# crown-C.net
KiCad netlist of a schematic drawn in EAGLE
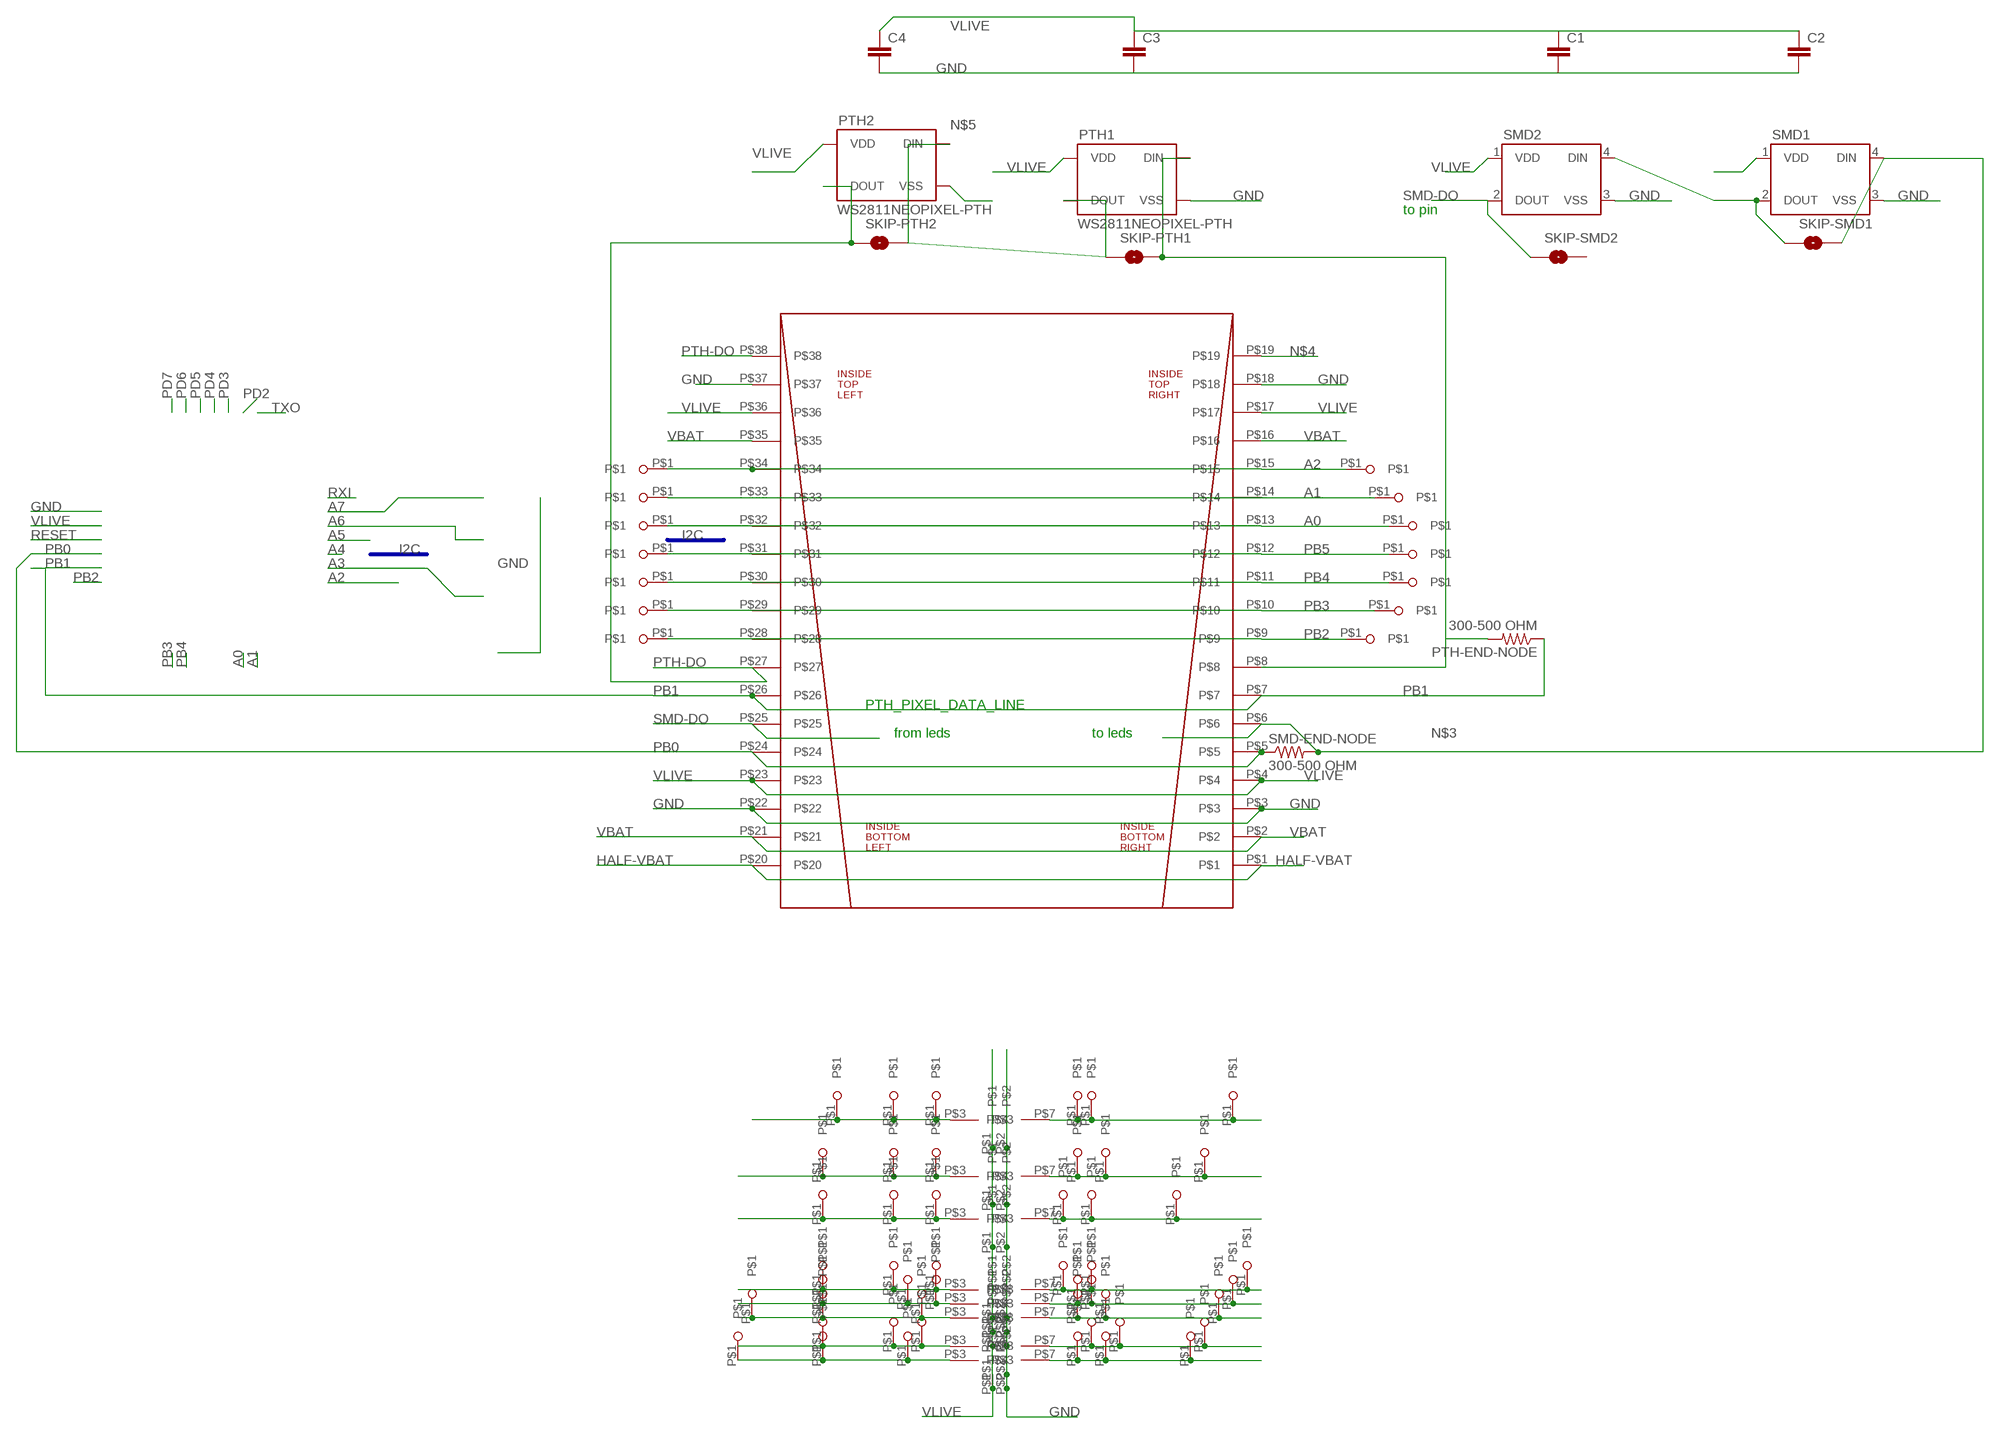
[diagram p0: schematic, sheet 1]

(export (version "E")
  (design (tool "Eeschema 10.0.6"))
  (components
    (comp (ref "C1")
      (value "CAP0805")
      (footprint "eagle-import:0805")
      (libsource (lib "eagle-import") (part "CAP0805"))
    )
    (comp (ref "C2")
      (value "CAP0805")
      (footprint "eagle-import:0805")
      (libsource (lib "eagle-import") (part "CAP0805"))
    )
    (comp (ref "C3")
      (value "CAP0805")
      (footprint "eagle-import:0805")
      (libsource (lib "eagle-import") (part "CAP0805"))
    )
    (comp (ref "C4")
      (value "CAP0805")
      (footprint "eagle-import:0805")
      (libsource (lib "eagle-import") (part "CAP0805"))
    )
    (comp (ref "PTH-END-NODE")
      (value "300-500 OHM")
      (footprint "eagle-import:0805")
      (libsource (lib "eagle-import") (part "RESISTOR0805-RES"))
    )
    (comp (ref "PTH1")
      (value "WS2811NEOPIXEL-PTH")
      (footprint "eagle-import:WS2811-PTH-FLAT")
      (libsource (lib "eagle-import") (part "WS2811NEOPIXEL-PTH"))
    )
    (comp (ref "PTH2")
      (value "WS2811NEOPIXEL-PTH")
      (footprint "eagle-import:WS2811-PTH-FLAT")
      (libsource (lib "eagle-import") (part "WS2811NEOPIXEL-PTH"))
    )
    (comp (ref "SKIP-PTH1")
      (value "SOLDERJUMPERNC2")
      (footprint "eagle-import:SJ_2S-NOTRACE")
      (libsource (lib "eagle-import") (part "SOLDERJUMPERNC2"))
    )
    (comp (ref "SKIP-PTH2")
      (value "SOLDERJUMPERNC2")
      (footprint "eagle-import:SJ_2S-NOTRACE")
      (libsource (lib "eagle-import") (part "SOLDERJUMPERNC2"))
    )
    (comp (ref "SKIP-SMD1")
      (value "SOLDERJUMPERNC2")
      (footprint "eagle-import:SJ_2S-NOTRACE")
      (libsource (lib "eagle-import") (part "SOLDERJUMPERNC2"))
    )
    (comp (ref "SKIP-SMD2")
      (value "SOLDERJUMPERNC2")
      (footprint "eagle-import:SJ_2S-NOTRACE")
      (libsource (lib "eagle-import") (part "SOLDERJUMPERNC2"))
    )
    (comp (ref "SMD-END-NODE")
      (value "300-500 OHM")
      (footprint "eagle-import:0805")
      (libsource (lib "eagle-import") (part "RESISTOR0805-RES"))
    )
    (comp (ref "SMD1")
      (value "WS2812B")
      (footprint "eagle-import:WS2812B")
      (libsource (lib "eagle-import") (part "WS2812B"))
    )
    (comp (ref "SMD2")
      (value "WS2812B")
      (footprint "eagle-import:WS2812B")
      (libsource (lib "eagle-import") (part "WS2812B"))
    )
    (comp (ref "U$1")
      (value "SMD_BREADBOARD")
      (footprint "eagle-import:SMD_BREADBOARD_4X")
      (libsource (lib "eagle-import") (part "SMD_BREADBOARD"))
    )
    (comp (ref "U$2")
      (value "CROWNSTANDARD")
      (footprint "eagle-import:CROWN")
      (libsource (lib "eagle-import") (part "CROWNSTANDARD"))
    )
    (comp (ref "U$3")
      (value "SMD_BREADBOARD")
      (footprint "eagle-import:SMD_BREADBOARD_4X")
      (libsource (lib "eagle-import") (part "SMD_BREADBOARD"))
    )
    (comp (ref "U$4")
      (value "SMD_BREADBOARD")
      (footprint "eagle-import:SMD_BREADBOARD_4X")
      (libsource (lib "eagle-import") (part "SMD_BREADBOARD"))
    )
    (comp (ref "U$5")
      (value "SMD_BREADBOARD")
      (footprint "eagle-import:SMD_BREADBOARD_4X")
      (libsource (lib "eagle-import") (part "SMD_BREADBOARD"))
    )
    (comp (ref "U$6")
      (value "SMD_BREADBOARD")
      (footprint "eagle-import:SMD_BREADBOARD_4X")
      (libsource (lib "eagle-import") (part "SMD_BREADBOARD"))
    )
    (comp (ref "U$7")
      (value "SMD_BREADBOARD")
      (footprint "eagle-import:SMD_BREADBOARD_4X")
      (libsource (lib "eagle-import") (part "SMD_BREADBOARD"))
    )
    (comp (ref "U$8")
      (value "SMD_BREADBOARD")
      (footprint "eagle-import:SMD_BREADBOARD_4X")
      (libsource (lib "eagle-import") (part "SMD_BREADBOARD"))
    )
    (comp (ref "U$9")
      (value "SMD_BREADBOARD")
      (footprint "eagle-import:SMD_BREADBOARD_4X")
      (libsource (lib "eagle-import") (part "SMD_BREADBOARD"))
    )
    (comp (ref "U$10")
      (value "SMD_PAD")
      (footprint "eagle-import:SMD_BREADBOARD_PAD")
      (libsource (lib "eagle-import") (part "SMD_PAD"))
    )
    (comp (ref "U$11")
      (value "SMD_PAD")
      (footprint "eagle-import:SMD_BREADBOARD_PAD")
      (libsource (lib "eagle-import") (part "SMD_PAD"))
    )
    (comp (ref "U$12")
      (value "SMD_PAD")
      (footprint "eagle-import:SMD_BREADBOARD_PAD")
      (libsource (lib "eagle-import") (part "SMD_PAD"))
    )
    (comp (ref "U$13")
      (value "SMD_PAD")
      (footprint "eagle-import:SMD_BREADBOARD_PAD")
      (libsource (lib "eagle-import") (part "SMD_PAD"))
    )
    (comp (ref "U$14")
      (value "SMD_PAD")
      (footprint "eagle-import:SMD_BREADBOARD_PAD")
      (libsource (lib "eagle-import") (part "SMD_PAD"))
    )
    (comp (ref "U$15")
      (value "SMD_PAD")
      (footprint "eagle-import:SMD_BREADBOARD_PAD")
      (libsource (lib "eagle-import") (part "SMD_PAD"))
    )
    (comp (ref "U$16")
      (value "SMD_PAD")
      (footprint "eagle-import:SMD_BREADBOARD_PAD")
      (libsource (lib "eagle-import") (part "SMD_PAD"))
    )
    (comp (ref "U$17")
      (value "SMD_PAD")
      (footprint "eagle-import:SMD_BREADBOARD_PAD")
      (libsource (lib "eagle-import") (part "SMD_PAD"))
    )
    (comp (ref "U$18")
      (value "SMD_PAD")
      (footprint "eagle-import:SMD_BREADBOARD_PAD")
      (libsource (lib "eagle-import") (part "SMD_PAD"))
    )
    (comp (ref "U$19")
      (value "SMD_PAD")
      (footprint "eagle-import:SMD_BREADBOARD_PAD")
      (libsource (lib "eagle-import") (part "SMD_PAD"))
    )
    (comp (ref "U$20")
      (value "SMD_PAD")
      (footprint "eagle-import:SMD_BREADBOARD_PAD")
      (libsource (lib "eagle-import") (part "SMD_PAD"))
    )
    (comp (ref "U$21")
      (value "SMD_PAD")
      (footprint "eagle-import:SMD_BREADBOARD_PAD")
      (libsource (lib "eagle-import") (part "SMD_PAD"))
    )
    (comp (ref "U$22")
      (value "SMD_PAD")
      (footprint "eagle-import:SMD_BREADBOARD_PAD")
      (libsource (lib "eagle-import") (part "SMD_PAD"))
    )
    (comp (ref "U$23")
      (value "SMD_PAD")
      (footprint "eagle-import:SMD_BREADBOARD_PAD")
      (libsource (lib "eagle-import") (part "SMD_PAD"))
    )
    (comp (ref "U$24")
      (value "SMD_PAD")
      (footprint "eagle-import:SMD_BREADBOARD_PAD")
      (libsource (lib "eagle-import") (part "SMD_PAD"))
    )
    (comp (ref "U$25")
      (value "SMD_PAD")
      (footprint "eagle-import:SMD_BREADBOARD_PAD")
      (libsource (lib "eagle-import") (part "SMD_PAD"))
    )
    (comp (ref "U$26")
      (value "SMD_PAD")
      (footprint "eagle-import:SMD_BREADBOARD_PAD")
      (libsource (lib "eagle-import") (part "SMD_PAD"))
    )
    (comp (ref "U$27")
      (value "SMD_PAD")
      (footprint "eagle-import:SMD_BREADBOARD_PAD")
      (libsource (lib "eagle-import") (part "SMD_PAD"))
    )
    (comp (ref "U$28")
      (value "SMD_PAD")
      (footprint "eagle-import:SMD_BREADBOARD_PAD")
      (libsource (lib "eagle-import") (part "SMD_PAD"))
    )
    (comp (ref "U$29")
      (value "SMD_PAD")
      (footprint "eagle-import:SMD_BREADBOARD_PAD")
      (libsource (lib "eagle-import") (part "SMD_PAD"))
    )
    (comp (ref "U$30")
      (value "SMD_PAD")
      (footprint "eagle-import:SMD_BREADBOARD_PAD")
      (libsource (lib "eagle-import") (part "SMD_PAD"))
    )
    (comp (ref "U$31")
      (value "SMD_PAD")
      (footprint "eagle-import:SMD_BREADBOARD_PAD")
      (libsource (lib "eagle-import") (part "SMD_PAD"))
    )
    (comp (ref "U$32")
      (value "SMD_PAD")
      (footprint "eagle-import:SMD_BREADBOARD_PAD")
      (libsource (lib "eagle-import") (part "SMD_PAD"))
    )
    (comp (ref "U$33")
      (value "SMD_PAD")
      (footprint "eagle-import:SMD_BREADBOARD_PAD")
      (libsource (lib "eagle-import") (part "SMD_PAD"))
    )
    (comp (ref "U$34")
      (value "SMD_PAD")
      (footprint "eagle-import:SMD_BREADBOARD_PAD")
      (libsource (lib "eagle-import") (part "SMD_PAD"))
    )
    (comp (ref "U$35")
      (value "SMD_PAD")
      (footprint "eagle-import:SMD_BREADBOARD_PAD")
      (libsource (lib "eagle-import") (part "SMD_PAD"))
    )
    (comp (ref "U$36")
      (value "SMD_PAD")
      (footprint "eagle-import:SMD_BREADBOARD_PAD")
      (libsource (lib "eagle-import") (part "SMD_PAD"))
    )
    (comp (ref "U$37")
      (value "SMD_PAD")
      (footprint "eagle-import:SMD_BREADBOARD_PAD")
      (libsource (lib "eagle-import") (part "SMD_PAD"))
    )
    (comp (ref "U$38")
      (value "SMD_PAD")
      (footprint "eagle-import:SMD_BREADBOARD_PAD")
      (libsource (lib "eagle-import") (part "SMD_PAD"))
    )
    (comp (ref "U$39")
      (value "SMD_PAD")
      (footprint "eagle-import:SMD_BREADBOARD_PAD")
      (libsource (lib "eagle-import") (part "SMD_PAD"))
    )
    (comp (ref "U$40")
      (value "SMD_PAD")
      (footprint "eagle-import:SMD_BREADBOARD_PAD")
      (libsource (lib "eagle-import") (part "SMD_PAD"))
    )
    (comp (ref "U$41")
      (value "SMD_PAD")
      (footprint "eagle-import:SMD_BREADBOARD_PAD")
      (libsource (lib "eagle-import") (part "SMD_PAD"))
    )
    (comp (ref "U$42")
      (value "SMD_PAD")
      (footprint "eagle-import:SMD_BREADBOARD_PAD")
      (libsource (lib "eagle-import") (part "SMD_PAD"))
    )
    (comp (ref "U$43")
      (value "SMD_PAD")
      (footprint "eagle-import:SMD_BREADBOARD_PAD")
      (libsource (lib "eagle-import") (part "SMD_PAD"))
    )
    (comp (ref "U$44")
      (value "SMD_PAD")
      (footprint "eagle-import:SMD_BREADBOARD_PAD")
      (libsource (lib "eagle-import") (part "SMD_PAD"))
    )
    (comp (ref "U$45")
      (value "SMD_PAD")
      (footprint "eagle-import:SMD_BREADBOARD_PAD")
      (libsource (lib "eagle-import") (part "SMD_PAD"))
    )
    (comp (ref "U$46")
      (value "SMD_PAD")
      (footprint "eagle-import:SMD_BREADBOARD_PAD")
      (libsource (lib "eagle-import") (part "SMD_PAD"))
    )
    (comp (ref "U$47")
      (value "SMD_PAD")
      (footprint "eagle-import:SMD_BREADBOARD_PAD")
      (libsource (lib "eagle-import") (part "SMD_PAD"))
    )
    (comp (ref "U$48")
      (value "SMD_PAD")
      (footprint "eagle-import:SMD_BREADBOARD_PAD")
      (libsource (lib "eagle-import") (part "SMD_PAD"))
    )
    (comp (ref "U$49")
      (value "SMD_PAD")
      (footprint "eagle-import:SMD_BREADBOARD_PAD")
      (libsource (lib "eagle-import") (part "SMD_PAD"))
    )
    (comp (ref "U$50")
      (value "SMD_PAD")
      (footprint "eagle-import:SMD_BREADBOARD_PAD")
      (libsource (lib "eagle-import") (part "SMD_PAD"))
    )
    (comp (ref "U$51")
      (value "SMD_PAD")
      (footprint "eagle-import:SMD_BREADBOARD_PAD")
      (libsource (lib "eagle-import") (part "SMD_PAD"))
    )
    (comp (ref "U$52")
      (value "SMD_PAD")
      (footprint "eagle-import:SMD_BREADBOARD_PAD")
      (libsource (lib "eagle-import") (part "SMD_PAD"))
    )
    (comp (ref "U$53")
      (value "SMD_PAD")
      (footprint "eagle-import:SMD_BREADBOARD_PAD")
      (libsource (lib "eagle-import") (part "SMD_PAD"))
    )
    (comp (ref "U$54")
      (value "SMD_PAD")
      (footprint "eagle-import:SMD_BREADBOARD_PAD")
      (libsource (lib "eagle-import") (part "SMD_PAD"))
    )
    (comp (ref "U$55")
      (value "SMD_PAD")
      (footprint "eagle-import:SMD_BREADBOARD_PAD")
      (libsource (lib "eagle-import") (part "SMD_PAD"))
    )
    (comp (ref "U$56")
      (value "SMD_PAD")
      (footprint "eagle-import:SMD_BREADBOARD_PAD")
      (libsource (lib "eagle-import") (part "SMD_PAD"))
    )
    (comp (ref "U$57")
      (value "SMD_PAD")
      (footprint "eagle-import:SMD_BREADBOARD_PAD")
      (libsource (lib "eagle-import") (part "SMD_PAD"))
    )
    (comp (ref "U$58")
      (value "SMD_PAD")
      (footprint "eagle-import:SMD_BREADBOARD_PAD")
      (libsource (lib "eagle-import") (part "SMD_PAD"))
    )
    (comp (ref "U$59")
      (value "SMD_PAD")
      (footprint "eagle-import:SMD_BREADBOARD_PAD")
      (libsource (lib "eagle-import") (part "SMD_PAD"))
    )
    (comp (ref "U$60")
      (value "SMD_PAD")
      (footprint "eagle-import:SMD_BREADBOARD_PAD")
      (libsource (lib "eagle-import") (part "SMD_PAD"))
    )
    (comp (ref "U$61")
      (value "SMD_PAD")
      (footprint "eagle-import:SMD_BREADBOARD_PAD")
      (libsource (lib "eagle-import") (part "SMD_PAD"))
    )
    (comp (ref "U$62")
      (value "SMD_PAD")
      (footprint "eagle-import:SMD_BREADBOARD_PAD")
      (libsource (lib "eagle-import") (part "SMD_PAD"))
    )
    (comp (ref "U$63")
      (value "SMD_PAD")
      (footprint "eagle-import:SMD_BREADBOARD_PAD")
      (libsource (lib "eagle-import") (part "SMD_PAD"))
    )
    (comp (ref "U$64")
      (value "SMD_PAD")
      (footprint "eagle-import:SMD_BREADBOARD_PAD")
      (libsource (lib "eagle-import") (part "SMD_PAD"))
    )
    (comp (ref "U$65")
      (value "SMD_PAD")
      (footprint "eagle-import:SMD_BREADBOARD_PAD")
      (libsource (lib "eagle-import") (part "SMD_PAD"))
    )
    (comp (ref "U$66")
      (value "SMD_PAD")
      (footprint "eagle-import:SMD_BREADBOARD_PAD")
      (libsource (lib "eagle-import") (part "SMD_PAD"))
    )
    (comp (ref "U$67")
      (value "SMD_PAD")
      (footprint "eagle-import:SMD_BREADBOARD_PAD")
      (libsource (lib "eagle-import") (part "SMD_PAD"))
    )
    (comp (ref "U$68")
      (value "SMD_PAD")
      (footprint "eagle-import:SMD_BREADBOARD_PAD")
      (libsource (lib "eagle-import") (part "SMD_PAD"))
    )
    (comp (ref "U$69")
      (value "SMD_PAD")
      (footprint "eagle-import:SMD_BREADBOARD_PAD")
      (libsource (lib "eagle-import") (part "SMD_PAD"))
    )
    (comp (ref "U$70")
      (value "SMD_PAD")
      (footprint "eagle-import:SMD_BREADBOARD_PAD")
      (libsource (lib "eagle-import") (part "SMD_PAD"))
    )
    (comp (ref "U$71")
      (value "SMD_PAD")
      (footprint "eagle-import:SMD_BREADBOARD_PAD")
      (libsource (lib "eagle-import") (part "SMD_PAD"))
    )
  )
  (nets
    (net (code "2") (name "/A0") (class "Default")
      (node (ref "U$2") (pin "P$13") (pinfunction "P$13_P$13") (pintype "bidirectional"))
      (node (ref "U$2") (pin "P$32") (pinfunction "P$32_P$32") (pintype "bidirectional"))
      (node (ref "U$44") (pin "P$1") (pinfunction "P$1_P$1") (pintype "bidirectional"))
      (node (ref "U$55") (pin "P$1") (pinfunction "P$1_P$1") (pintype "bidirectional"))
    )
    (net (code "3") (name "/A1") (class "Default")
      (node (ref "U$2") (pin "P$14") (pinfunction "P$14_P$14") (pintype "bidirectional"))
      (node (ref "U$2") (pin "P$33") (pinfunction "P$33_P$33") (pintype "bidirectional"))
      (node (ref "U$43") (pin "P$1") (pinfunction "P$1_P$1") (pintype "bidirectional"))
      (node (ref "U$56") (pin "P$1") (pinfunction "P$1_P$1") (pintype "bidirectional"))
    )
    (net (code "4") (name "/A2") (class "Default")
      (node (ref "U$2") (pin "P$15") (pinfunction "P$15_P$15") (pintype "bidirectional"))
      (node (ref "U$2") (pin "P$34") (pinfunction "P$34_P$34") (pintype "bidirectional"))
      (node (ref "U$42") (pin "P$1") (pinfunction "P$1_P$1") (pintype "bidirectional"))
      (node (ref "U$58") (pin "P$1") (pinfunction "P$1_P$1") (pintype "bidirectional"))
    )
    (net (code "10") (name "/GND") (class "Default")
      (node (ref "C1") (pin "2") (pinfunction "2_2") (pintype "passive"))
      (node (ref "C2") (pin "2") (pinfunction "2_2") (pintype "passive"))
      (node (ref "C3") (pin "2") (pinfunction "2_2") (pintype "passive"))
      (node (ref "C4") (pin "2") (pinfunction "2_2") (pintype "passive"))
      (node (ref "PTH1") (pin "P$2") (pinfunction "VSS_P$2") (pintype "power_in"))
      (node (ref "PTH1") (pin "P$6") (pinfunction "VSS_P$6") (pintype "power_in"))
      (node (ref "PTH2") (pin "P$2") (pinfunction "VSS_P$2") (pintype "power_in"))
      (node (ref "PTH2") (pin "P$6") (pinfunction "VSS_P$6") (pintype "power_in"))
      (node (ref "SMD1") (pin "3") (pinfunction "VSS_3") (pintype "power_in"))
      (node (ref "SMD2") (pin "3") (pinfunction "VSS_3") (pintype "power_in"))
      (node (ref "U$1") (pin "P$2") (pinfunction "P$2_P$2") (pintype "bidirectional"))
      (node (ref "U$2") (pin "P$18") (pinfunction "P$18_P$18") (pintype "bidirectional"))
      (node (ref "U$2") (pin "P$22") (pinfunction "P$22_P$22") (pintype "bidirectional"))
      (node (ref "U$2") (pin "P$3") (pinfunction "P$3_P$3") (pintype "bidirectional"))
      (node (ref "U$2") (pin "P$37") (pinfunction "P$37_P$37") (pintype "bidirectional"))
      (node (ref "U$3") (pin "P$2") (pinfunction "P$2_P$2") (pintype "bidirectional"))
      (node (ref "U$4") (pin "P$2") (pinfunction "P$2_P$2") (pintype "bidirectional"))
      (node (ref "U$5") (pin "P$2") (pinfunction "P$2_P$2") (pintype "bidirectional"))
      (node (ref "U$6") (pin "P$2") (pinfunction "P$2_P$2") (pintype "bidirectional"))
      (node (ref "U$7") (pin "P$2") (pinfunction "P$2_P$2") (pintype "bidirectional"))
      (node (ref "U$8") (pin "P$2") (pinfunction "P$2_P$2") (pintype "bidirectional"))
      (node (ref "U$9") (pin "P$2") (pinfunction "P$2_P$2") (pintype "bidirectional"))
    )
    (net (code "11") (name "/HALF-VBAT") (class "Default")
      (node (ref "U$2") (pin "P$1") (pinfunction "P$1_P$1") (pintype "bidirectional"))
      (node (ref "U$2") (pin "P$20") (pinfunction "P$20_P$20") (pintype "bidirectional"))
    )
    (net (code "12") (name "/N$3") (class "Default")
      (node (ref "SKIP-SMD1") (pin "2") (pinfunction "2_2") (pintype "passive"))
      (node (ref "SMD-END-NODE") (pin "2") (pinfunction "2_2") (pintype "passive"))
      (node (ref "SMD1") (pin "4") (pinfunction "DIN_4") (pintype "input"))
      (node (ref "U$2") (pin "P$6") (pinfunction "P$6_P$6") (pintype "bidirectional"))
    )
    (net (code "13") (name "/N$4") (class "Default")
      (node (ref "PTH-END-NODE") (pin "2") (pinfunction "2_2") (pintype "passive"))
      (node (ref "PTH1") (pin "P$4") (pinfunction "DIN_P$4") (pintype "input"))
      (node (ref "PTH1") (pin "P$8") (pinfunction "DIN_P$8") (pintype "input"))
      (node (ref "SKIP-PTH1") (pin "2") (pinfunction "2_2") (pintype "passive"))
      (node (ref "U$2") (pin "P$19") (pinfunction "P$19_P$19") (pintype "bidirectional"))
      (node (ref "U$2") (pin "P$8") (pinfunction "P$8_P$8") (pintype "bidirectional"))
    )
    (net (code "14") (name "/N$5") (class "Default")
      (node (ref "PTH1") (pin "P$1") (pinfunction "DOUT_P$1") (pintype "output"))
      (node (ref "PTH1") (pin "P$5") (pinfunction "DOUT_P$5") (pintype "output"))
      (node (ref "PTH2") (pin "P$4") (pinfunction "DIN_P$4") (pintype "input"))
      (node (ref "PTH2") (pin "P$8") (pinfunction "DIN_P$8") (pintype "input"))
      (node (ref "SKIP-PTH1") (pin "1") (pinfunction "1_1") (pintype "passive"))
      (node (ref "SKIP-PTH2") (pin "2") (pinfunction "2_2") (pintype "passive"))
    )
    (net (code "15") (name "/PB0") (class "Default")
      (node (ref "SMD-END-NODE") (pin "1") (pinfunction "1_1") (pintype "passive"))
      (node (ref "U$2") (pin "P$24") (pinfunction "P$24_P$24") (pintype "bidirectional"))
      (node (ref "U$2") (pin "P$5") (pinfunction "P$5_P$5") (pintype "bidirectional"))
    )
    (net (code "16") (name "/PB1") (class "Default")
      (node (ref "PTH-END-NODE") (pin "1") (pinfunction "1_1") (pintype "passive"))
      (node (ref "U$2") (pin "P$26") (pinfunction "P$26_P$26") (pintype "bidirectional"))
      (node (ref "U$2") (pin "P$7") (pinfunction "P$7_P$7") (pintype "bidirectional"))
    )
    (net (code "17") (name "/PB2") (class "Default")
      (node (ref "U$2") (pin "P$28") (pinfunction "P$28_P$28") (pintype "bidirectional"))
      (node (ref "U$2") (pin "P$9") (pinfunction "P$9_P$9") (pintype "bidirectional"))
      (node (ref "U$48") (pin "P$1") (pinfunction "P$1_P$1") (pintype "bidirectional"))
      (node (ref "U$51") (pin "P$1") (pinfunction "P$1_P$1") (pintype "bidirectional"))
    )
    (net (code "18") (name "/PB3") (class "Default")
      (node (ref "U$2") (pin "P$10") (pinfunction "P$10_P$10") (pintype "bidirectional"))
      (node (ref "U$2") (pin "P$29") (pinfunction "P$29_P$29") (pintype "bidirectional"))
      (node (ref "U$47") (pin "P$1") (pinfunction "P$1_P$1") (pintype "bidirectional"))
      (node (ref "U$52") (pin "P$1") (pinfunction "P$1_P$1") (pintype "bidirectional"))
    )
    (net (code "19") (name "/PB4") (class "Default")
      (node (ref "U$2") (pin "P$11") (pinfunction "P$11_P$11") (pintype "bidirectional"))
      (node (ref "U$2") (pin "P$30") (pinfunction "P$30_P$30") (pintype "bidirectional"))
      (node (ref "U$46") (pin "P$1") (pinfunction "P$1_P$1") (pintype "bidirectional"))
      (node (ref "U$53") (pin "P$1") (pinfunction "P$1_P$1") (pintype "bidirectional"))
    )
    (net (code "20") (name "/PB5") (class "Default")
      (node (ref "U$2") (pin "P$12") (pinfunction "P$12_P$12") (pintype "bidirectional"))
      (node (ref "U$2") (pin "P$31") (pinfunction "P$31_P$31") (pintype "bidirectional"))
      (node (ref "U$45") (pin "P$1") (pinfunction "P$1_P$1") (pintype "bidirectional"))
      (node (ref "U$54") (pin "P$1") (pinfunction "P$1_P$1") (pintype "bidirectional"))
    )
    (net (code "27") (name "/PTH-DO") (class "Default")
      (node (ref "PTH2") (pin "P$1") (pinfunction "DOUT_P$1") (pintype "output"))
      (node (ref "PTH2") (pin "P$5") (pinfunction "DOUT_P$5") (pintype "output"))
      (node (ref "SKIP-PTH2") (pin "1") (pinfunction "1_1") (pintype "passive"))
      (node (ref "U$2") (pin "P$27") (pinfunction "P$27_P$27") (pintype "bidirectional"))
      (node (ref "U$2") (pin "P$38") (pinfunction "P$38_P$38") (pintype "bidirectional"))
    )
    (net (code "30") (name "/SMD-DO") (class "Default")
      (node (ref "SKIP-SMD2") (pin "1") (pinfunction "1_1") (pintype "passive"))
      (node (ref "SMD2") (pin "2") (pinfunction "DOUT_2") (pintype "output"))
      (node (ref "U$2") (pin "P$25") (pinfunction "P$25_P$25") (pintype "bidirectional"))
    )
    (net (code "32") (name "/VBAT") (class "Default")
      (node (ref "U$2") (pin "P$16") (pinfunction "P$16_P$16") (pintype "bidirectional"))
      (node (ref "U$2") (pin "P$2") (pinfunction "P$2_P$2") (pintype "bidirectional"))
      (node (ref "U$2") (pin "P$21") (pinfunction "P$21_P$21") (pintype "bidirectional"))
      (node (ref "U$2") (pin "P$35") (pinfunction "P$35_P$35") (pintype "bidirectional"))
    )
    (net (code "33") (name "/VLIVE") (class "Default")
      (node (ref "C1") (pin "1") (pinfunction "1_1") (pintype "passive"))
      (node (ref "C2") (pin "1") (pinfunction "1_1") (pintype "passive"))
      (node (ref "C3") (pin "1") (pinfunction "1_1") (pintype "passive"))
      (node (ref "C4") (pin "1") (pinfunction "1_1") (pintype "passive"))
      (node (ref "PTH1") (pin "P$3") (pinfunction "VDD_P$3") (pintype "power_in"))
      (node (ref "PTH1") (pin "P$7") (pinfunction "VDD_P$7") (pintype "power_in"))
      (node (ref "PTH2") (pin "P$3") (pinfunction "VDD_P$3") (pintype "power_in"))
      (node (ref "PTH2") (pin "P$7") (pinfunction "VDD_P$7") (pintype "power_in"))
      (node (ref "SMD1") (pin "1") (pinfunction "VDD_1") (pintype "power_in"))
      (node (ref "SMD2") (pin "1") (pinfunction "VDD_1") (pintype "power_in"))
      (node (ref "U$1") (pin "P$1") (pinfunction "P$1_P$1") (pintype "bidirectional"))
      (node (ref "U$2") (pin "P$17") (pinfunction "P$17_P$17") (pintype "bidirectional"))
      (node (ref "U$2") (pin "P$23") (pinfunction "P$23_P$23") (pintype "bidirectional"))
      (node (ref "U$2") (pin "P$36") (pinfunction "P$36_P$36") (pintype "bidirectional"))
      (node (ref "U$2") (pin "P$4") (pinfunction "P$4_P$4") (pintype "bidirectional"))
      (node (ref "U$3") (pin "P$1") (pinfunction "P$1_P$1") (pintype "bidirectional"))
      (node (ref "U$4") (pin "P$1") (pinfunction "P$1_P$1") (pintype "bidirectional"))
      (node (ref "U$5") (pin "P$1") (pinfunction "P$1_P$1") (pintype "bidirectional"))
      (node (ref "U$6") (pin "P$1") (pinfunction "P$1_P$1") (pintype "bidirectional"))
      (node (ref "U$7") (pin "P$1") (pinfunction "P$1_P$1") (pintype "bidirectional"))
      (node (ref "U$8") (pin "P$1") (pinfunction "P$1_P$1") (pintype "bidirectional"))
      (node (ref "U$9") (pin "P$1") (pinfunction "P$1_P$1") (pintype "bidirectional"))
    )
    (net (code "35") (name "Net-(SMD1-DOUT)") (class "Default")
      (node (ref "SKIP-SMD1") (pin "1") (pinfunction "1_1") (pintype "passive"))
      (node (ref "SMD1") (pin "2") (pinfunction "DOUT_2") (pintype "output"))
      (node (ref "SMD2") (pin "4") (pinfunction "DIN_4") (pintype "input"))
    )
    (net (code "36") (name "Net-(U$1-P$4)") (class "Default")
      (node (ref "U$1") (pin "P$7") (pinfunction "P$4_P$7") (pintype "bidirectional"))
      (node (ref "U$26") (pin "P$1") (pinfunction "P$1_P$1") (pintype "bidirectional"))
      (node (ref "U$27") (pin "P$1") (pinfunction "P$1_P$1") (pintype "bidirectional"))
      (node (ref "U$64") (pin "P$1") (pinfunction "P$1_P$1") (pintype "bidirectional"))
    )
    (net (code "37") (name "Net-(U$1-PadP$3)") (class "Default")
      (node (ref "U$1") (pin "P$3") (pinfunction "P$3_P$3") (pintype "bidirectional"))
      (node (ref "U$24") (pin "P$1") (pinfunction "P$1_P$1") (pintype "bidirectional"))
      (node (ref "U$25") (pin "P$1") (pinfunction "P$1_P$1") (pintype "bidirectional"))
      (node (ref "U$63") (pin "P$1") (pinfunction "P$1_P$1") (pintype "bidirectional"))
    )
    (net (code "38") (name "Net-(U$3-P$4)") (class "Default")
      (node (ref "U$28") (pin "P$1") (pinfunction "P$1_P$1") (pintype "bidirectional"))
      (node (ref "U$29") (pin "P$1") (pinfunction "P$1_P$1") (pintype "bidirectional"))
      (node (ref "U$3") (pin "P$7") (pinfunction "P$4_P$7") (pintype "bidirectional"))
      (node (ref "U$65") (pin "P$1") (pinfunction "P$1_P$1") (pintype "bidirectional"))
    )
    (net (code "39") (name "Net-(U$4-P$4)") (class "Default")
      (node (ref "U$34") (pin "P$1") (pinfunction "P$1_P$1") (pintype "bidirectional"))
      (node (ref "U$35") (pin "P$1") (pinfunction "P$1_P$1") (pintype "bidirectional"))
      (node (ref "U$4") (pin "P$7") (pinfunction "P$4_P$7") (pintype "bidirectional"))
      (node (ref "U$68") (pin "P$1") (pinfunction "P$1_P$1") (pintype "bidirectional"))
    )
    (net (code "40") (name "Net-(U$5-P$4)") (class "Default")
      (node (ref "U$36") (pin "P$1") (pinfunction "P$1_P$1") (pintype "bidirectional"))
      (node (ref "U$37") (pin "P$1") (pinfunction "P$1_P$1") (pintype "bidirectional"))
      (node (ref "U$5") (pin "P$7") (pinfunction "P$4_P$7") (pintype "bidirectional"))
      (node (ref "U$69") (pin "P$1") (pinfunction "P$1_P$1") (pintype "bidirectional"))
    )
    (net (code "41") (name "Net-(U$6-P$4)") (class "Default")
      (node (ref "U$38") (pin "P$1") (pinfunction "P$1_P$1") (pintype "bidirectional"))
      (node (ref "U$39") (pin "P$1") (pinfunction "P$1_P$1") (pintype "bidirectional"))
      (node (ref "U$6") (pin "P$7") (pinfunction "P$4_P$7") (pintype "bidirectional"))
      (node (ref "U$70") (pin "P$1") (pinfunction "P$1_P$1") (pintype "bidirectional"))
    )
    (net (code "42") (name "Net-(U$7-P$4)") (class "Default")
      (node (ref "U$40") (pin "P$1") (pinfunction "P$1_P$1") (pintype "bidirectional"))
      (node (ref "U$41") (pin "P$1") (pinfunction "P$1_P$1") (pintype "bidirectional"))
      (node (ref "U$7") (pin "P$7") (pinfunction "P$4_P$7") (pintype "bidirectional"))
      (node (ref "U$71") (pin "P$1") (pinfunction "P$1_P$1") (pintype "bidirectional"))
    )
    (net (code "43") (name "Net-(U$8-P$4)") (class "Default")
      (node (ref "U$32") (pin "P$1") (pinfunction "P$1_P$1") (pintype "bidirectional"))
      (node (ref "U$33") (pin "P$1") (pinfunction "P$1_P$1") (pintype "bidirectional"))
      (node (ref "U$67") (pin "P$1") (pinfunction "P$1_P$1") (pintype "bidirectional"))
      (node (ref "U$8") (pin "P$7") (pinfunction "P$4_P$7") (pintype "bidirectional"))
    )
    (net (code "44") (name "Net-(U$9-P$4)") (class "Default")
      (node (ref "U$30") (pin "P$1") (pinfunction "P$1_P$1") (pintype "bidirectional"))
      (node (ref "U$31") (pin "P$1") (pinfunction "P$1_P$1") (pintype "bidirectional"))
      (node (ref "U$66") (pin "P$1") (pinfunction "P$1_P$1") (pintype "bidirectional"))
      (node (ref "U$9") (pin "P$7") (pinfunction "P$4_P$7") (pintype "bidirectional"))
    )
    (net (code "45") (name "Net-(U$10-PadP$1)") (class "Default")
      (node (ref "U$10") (pin "P$1") (pinfunction "P$1_P$1") (pintype "bidirectional"))
      (node (ref "U$11") (pin "P$1") (pinfunction "P$1_P$1") (pintype "bidirectional"))
      (node (ref "U$49") (pin "P$1") (pinfunction "P$1_P$1") (pintype "bidirectional"))
      (node (ref "U$7") (pin "P$3") (pinfunction "P$3_P$3") (pintype "bidirectional"))
    )
    (net (code "46") (name "Net-(U$12-PadP$1)") (class "Default")
      (node (ref "U$12") (pin "P$1") (pinfunction "P$1_P$1") (pintype "bidirectional"))
      (node (ref "U$13") (pin "P$1") (pinfunction "P$1_P$1") (pintype "bidirectional"))
      (node (ref "U$50") (pin "P$1") (pinfunction "P$1_P$1") (pintype "bidirectional"))
      (node (ref "U$6") (pin "P$3") (pinfunction "P$3_P$3") (pintype "bidirectional"))
    )
    (net (code "47") (name "Net-(U$14-PadP$1)") (class "Default")
      (node (ref "U$14") (pin "P$1") (pinfunction "P$1_P$1") (pintype "bidirectional"))
      (node (ref "U$15") (pin "P$1") (pinfunction "P$1_P$1") (pintype "bidirectional"))
      (node (ref "U$5") (pin "P$3") (pinfunction "P$3_P$3") (pintype "bidirectional"))
      (node (ref "U$57") (pin "P$1") (pinfunction "P$1_P$1") (pintype "bidirectional"))
    )
    (net (code "48") (name "Net-(U$16-PadP$1)") (class "Default")
      (node (ref "U$16") (pin "P$1") (pinfunction "P$1_P$1") (pintype "bidirectional"))
      (node (ref "U$17") (pin "P$1") (pinfunction "P$1_P$1") (pintype "bidirectional"))
      (node (ref "U$4") (pin "P$3") (pinfunction "P$3_P$3") (pintype "bidirectional"))
      (node (ref "U$59") (pin "P$1") (pinfunction "P$1_P$1") (pintype "bidirectional"))
    )
    (net (code "49") (name "Net-(U$18-PadP$1)") (class "Default")
      (node (ref "U$18") (pin "P$1") (pinfunction "P$1_P$1") (pintype "bidirectional"))
      (node (ref "U$19") (pin "P$1") (pinfunction "P$1_P$1") (pintype "bidirectional"))
      (node (ref "U$60") (pin "P$1") (pinfunction "P$1_P$1") (pintype "bidirectional"))
      (node (ref "U$8") (pin "P$3") (pinfunction "P$3_P$3") (pintype "bidirectional"))
    )
    (net (code "50") (name "Net-(U$20-PadP$1)") (class "Default")
      (node (ref "U$20") (pin "P$1") (pinfunction "P$1_P$1") (pintype "bidirectional"))
      (node (ref "U$21") (pin "P$1") (pinfunction "P$1_P$1") (pintype "bidirectional"))
      (node (ref "U$61") (pin "P$1") (pinfunction "P$1_P$1") (pintype "bidirectional"))
      (node (ref "U$9") (pin "P$3") (pinfunction "P$3_P$3") (pintype "bidirectional"))
    )
    (net (code "51") (name "Net-(U$22-PadP$1)") (class "Default")
      (node (ref "U$22") (pin "P$1") (pinfunction "P$1_P$1") (pintype "bidirectional"))
      (node (ref "U$23") (pin "P$1") (pinfunction "P$1_P$1") (pintype "bidirectional"))
      (node (ref "U$3") (pin "P$3") (pinfunction "P$3_P$3") (pintype "bidirectional"))
      (node (ref "U$62") (pin "P$1") (pinfunction "P$1_P$1") (pintype "bidirectional"))
    )
    (net (code "52") (name "unconnected-(SKIP-SMD2-Pad2)") (class "Default")
      (node (ref "SKIP-SMD2") (pin "2") (pinfunction "2_2") (pintype "passive"))
    )
  )
)
